# ProDoc_dogo-Lab_esp32c3__shockerMini_V1_.net
KiCad netlist of a schematic drawn in EasyEDA Pro
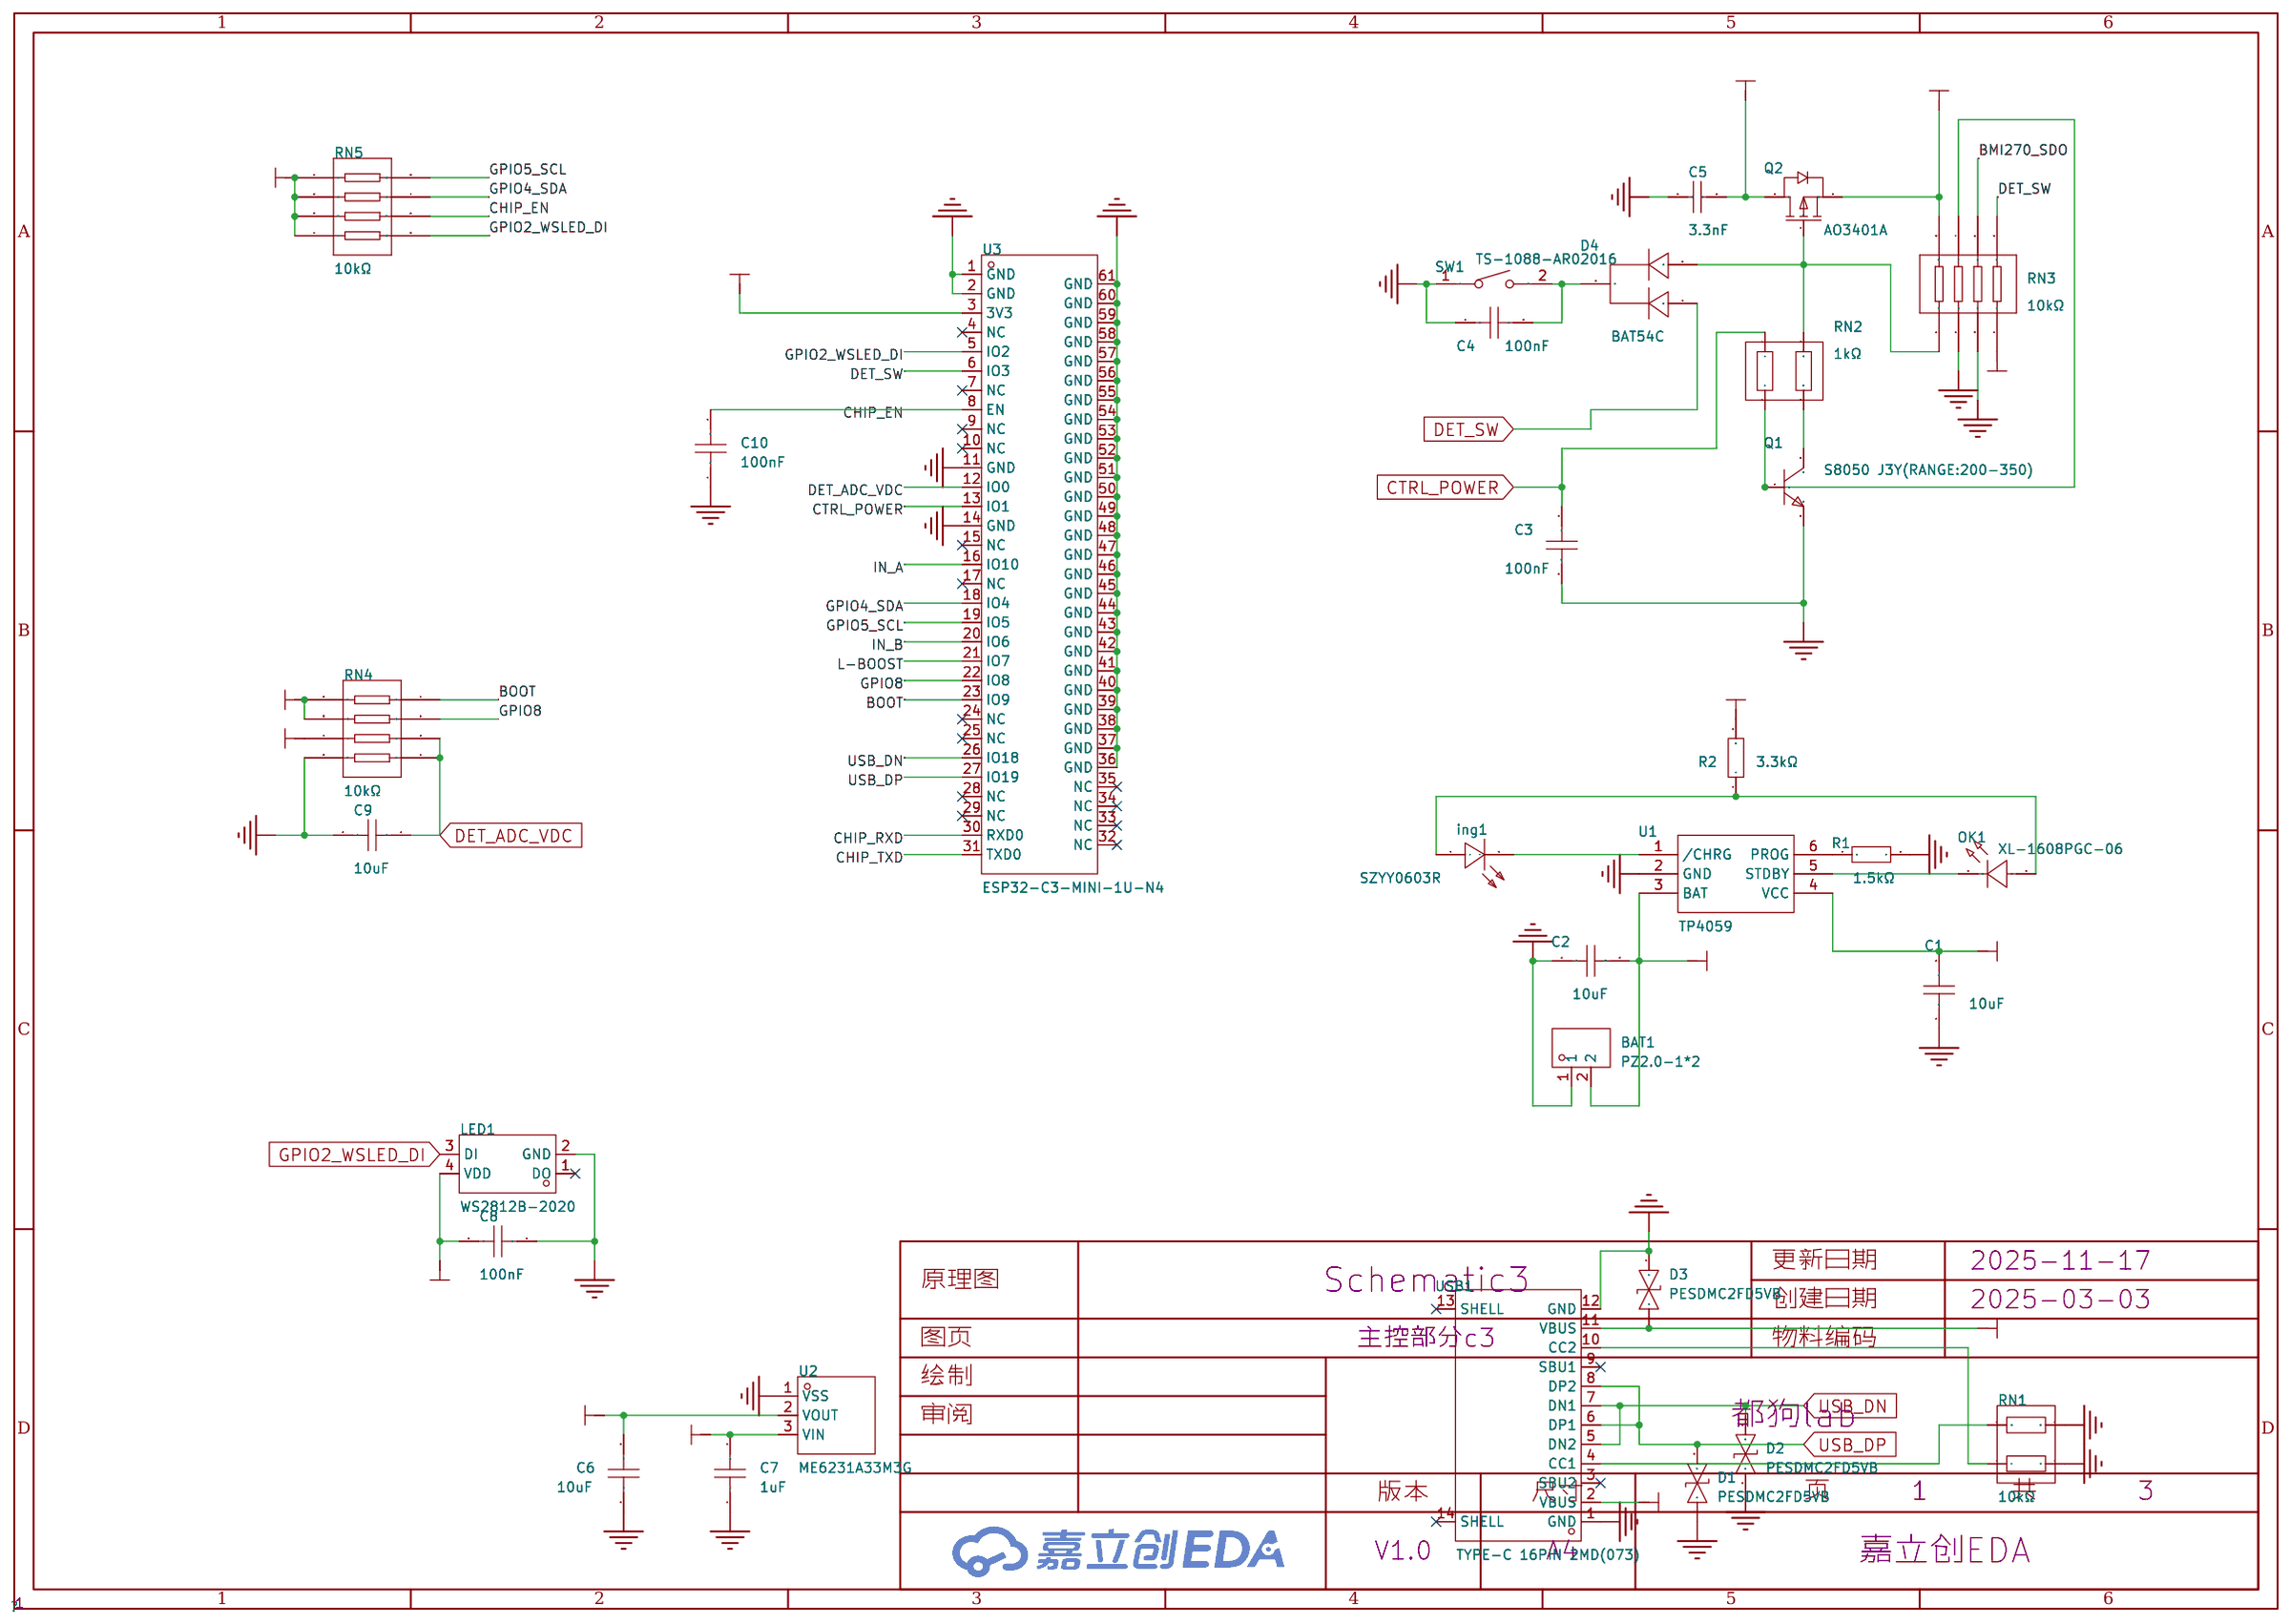
[diagram p0: 主控部分c3]
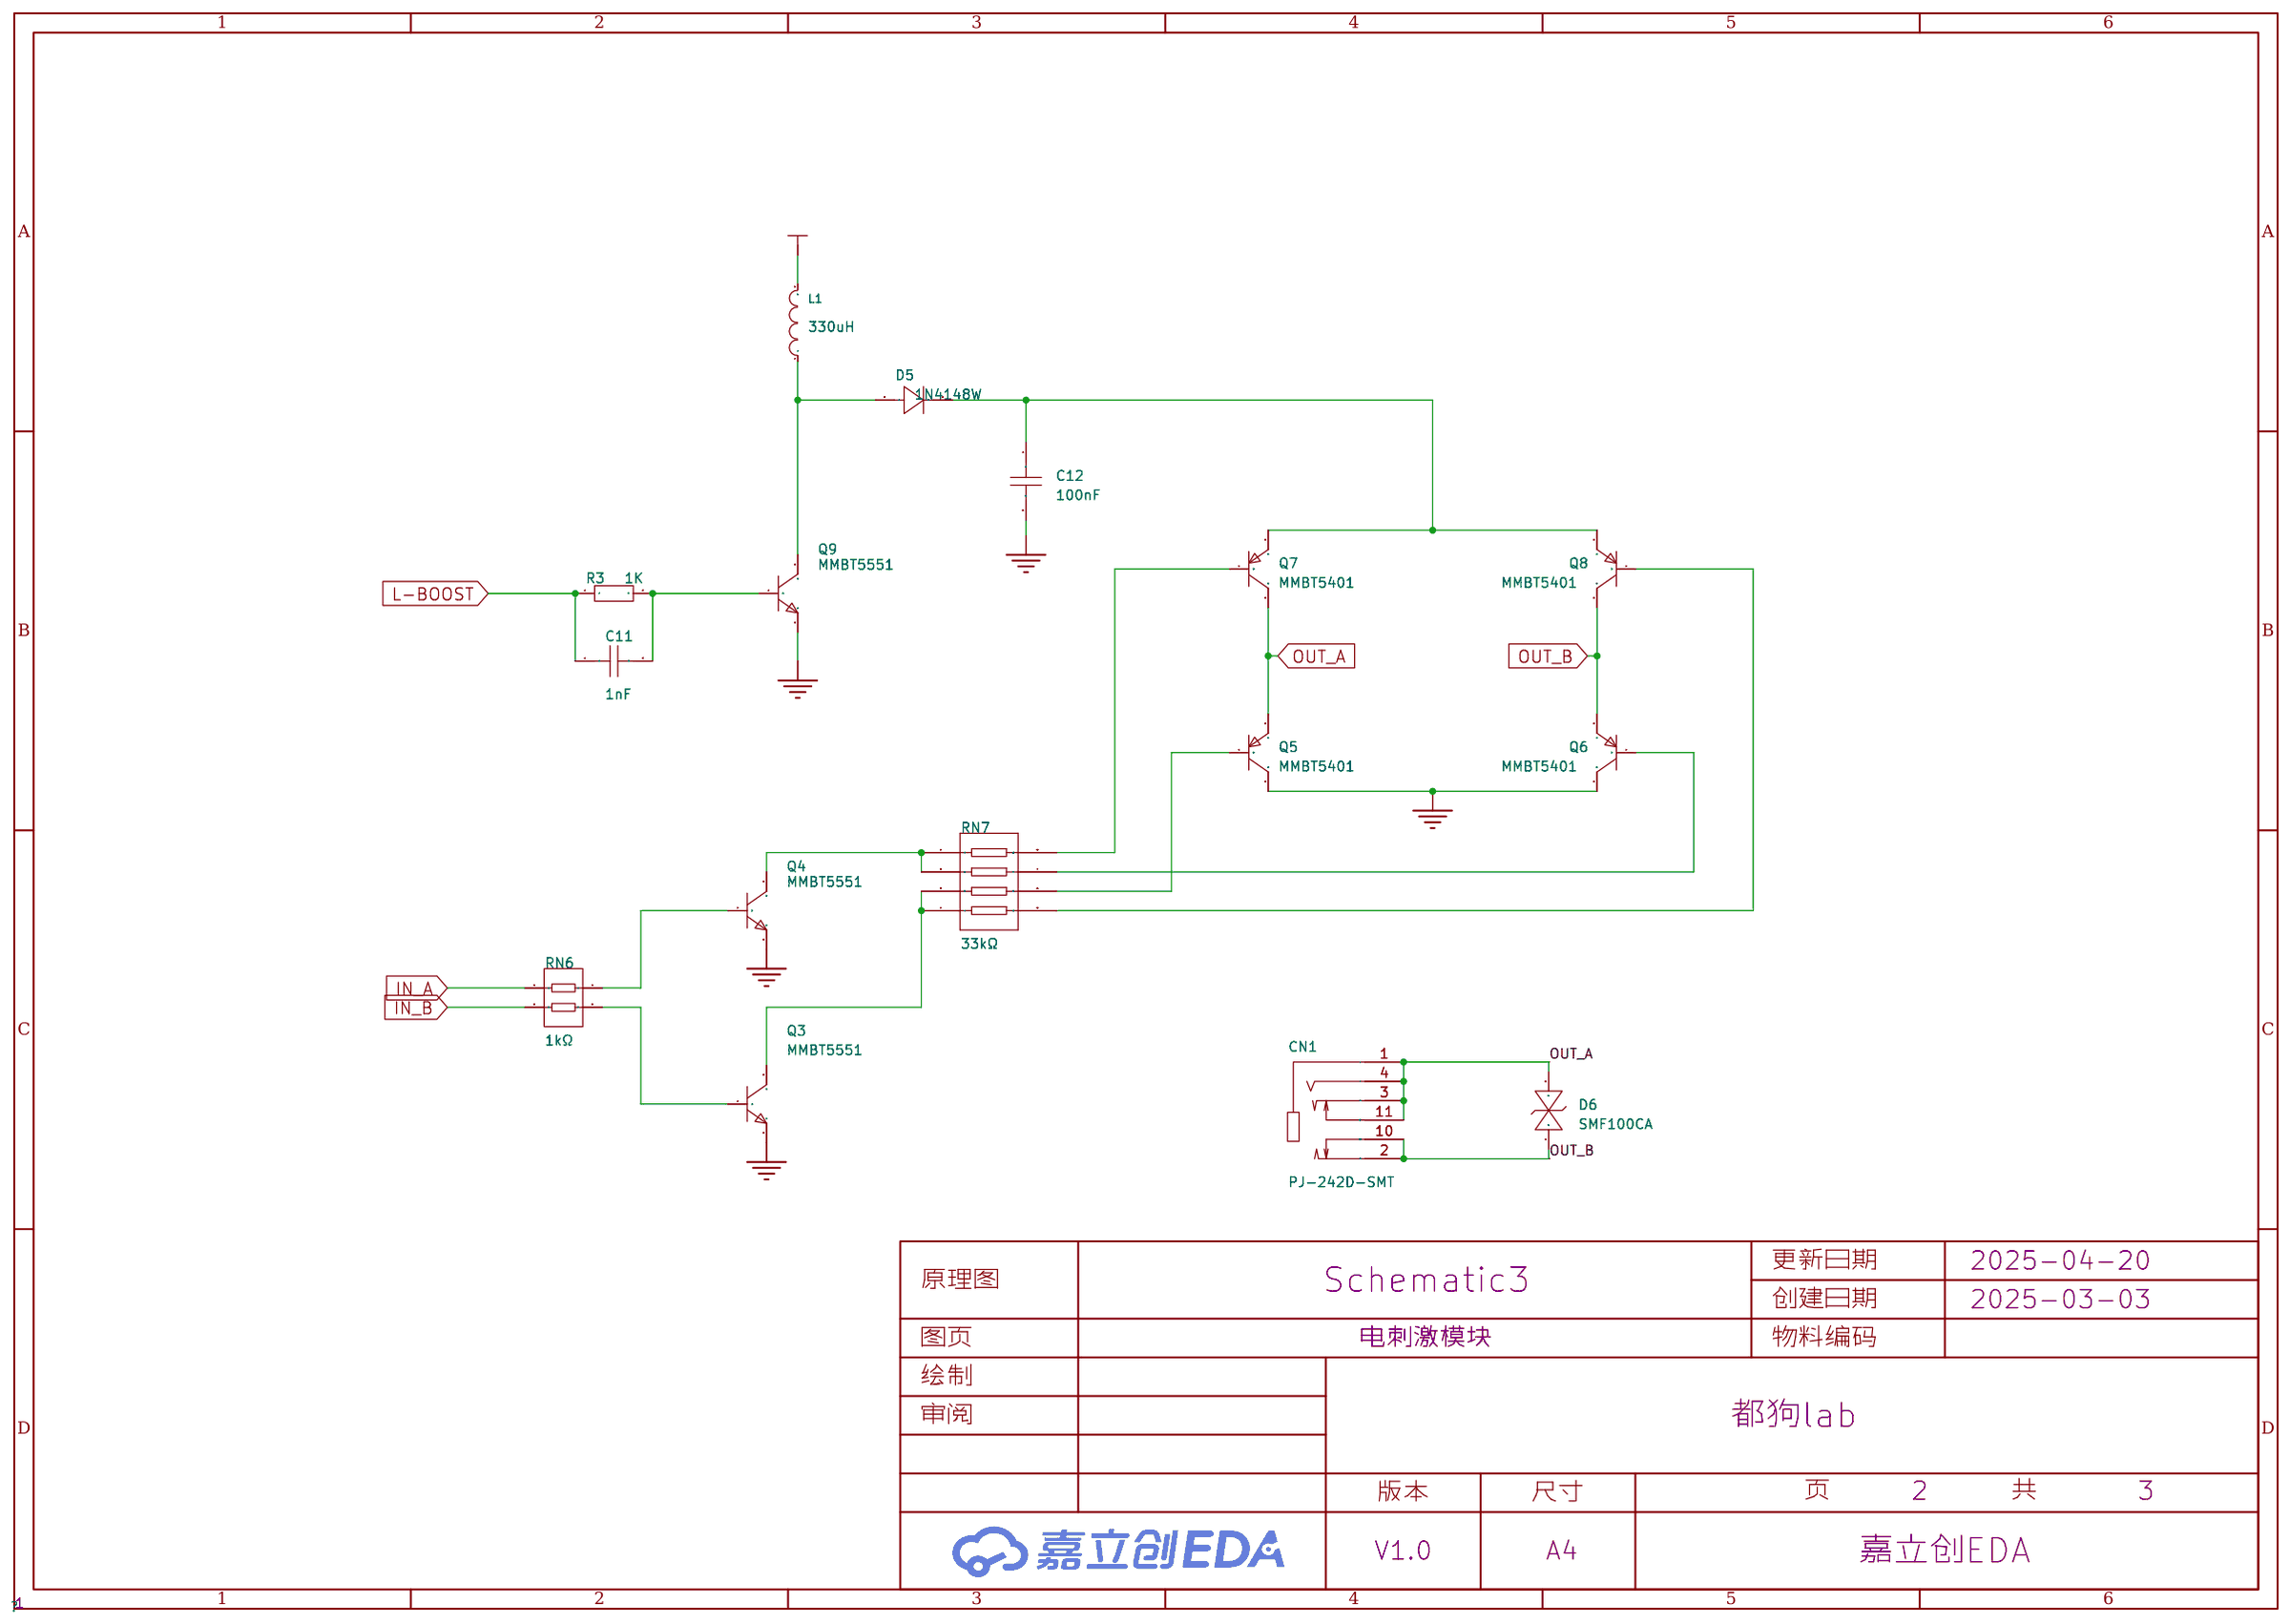
[diagram p1: 电刺激模块]
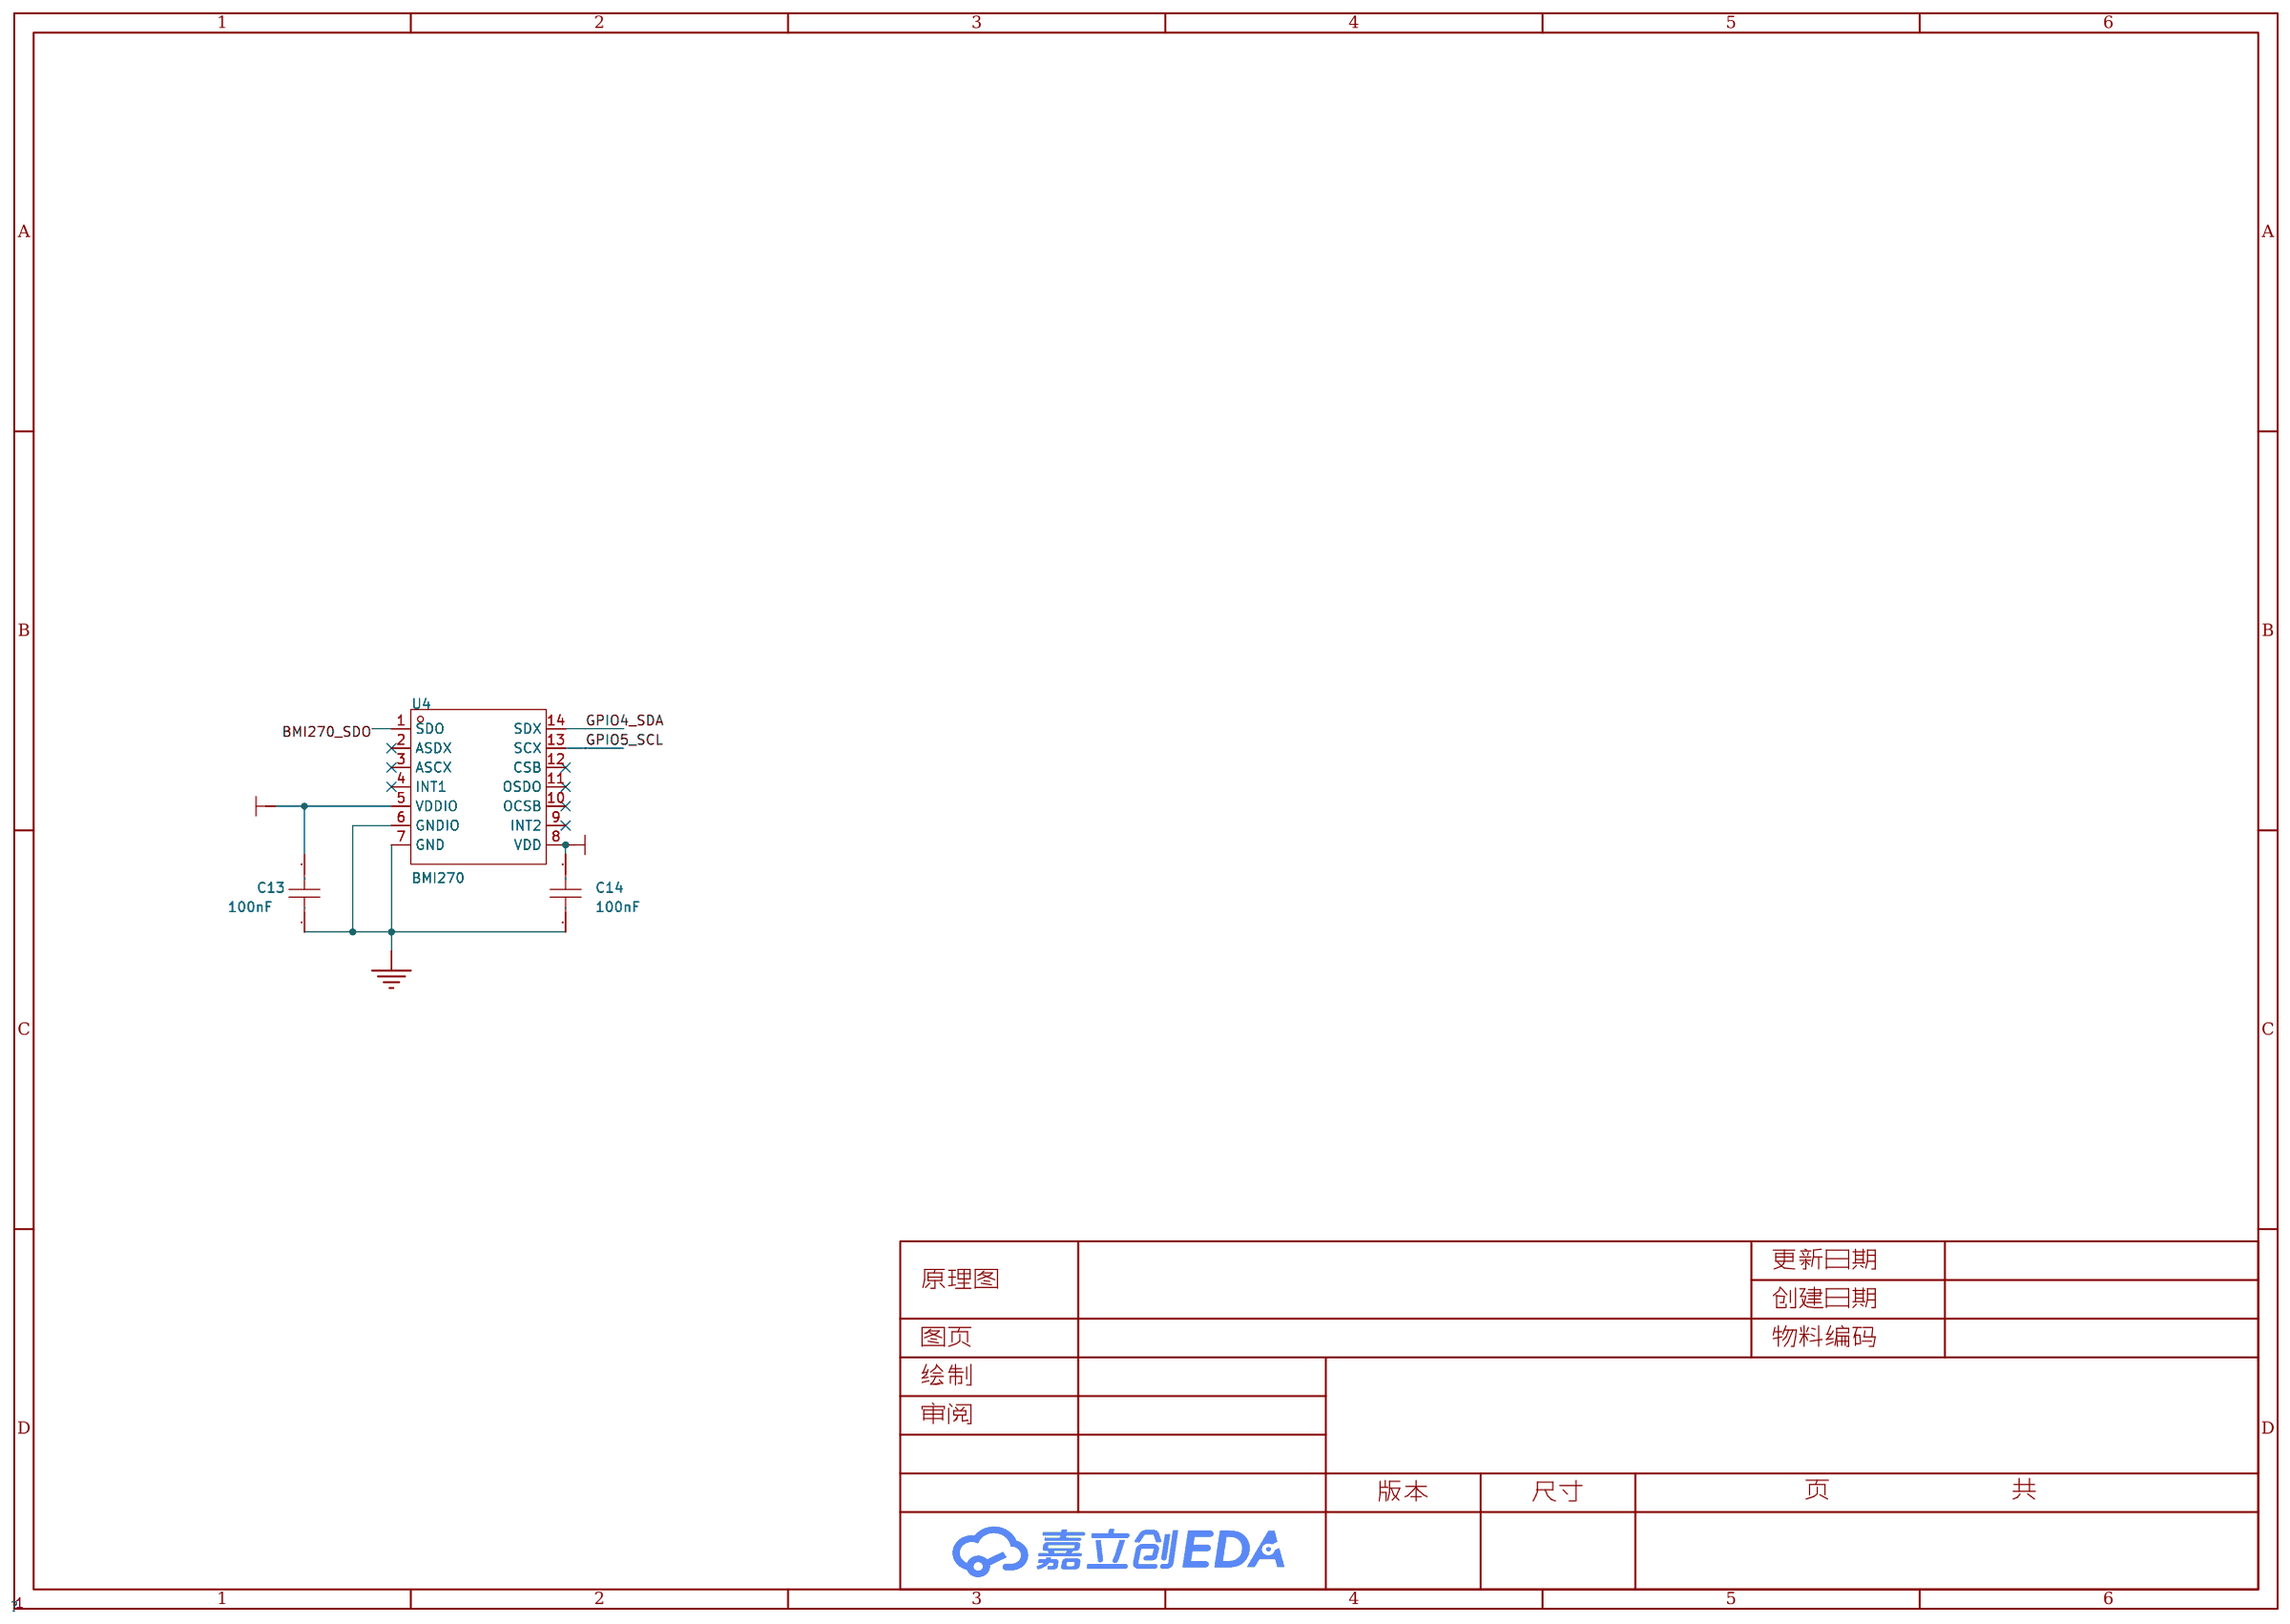
[diagram p2: 体动传感器]

(export (version "E")
  (design (tool "Eeschema 10.0.6"))
  (components
    (comp (ref "BAT1")
      (value "PZ2.0-1*2")
      (footprint "easyedapro:HDR-TH_2P-P2.00-V-M")
      (description "插针结构:1x2P;间距:2mm;安装类型:直插;排数:单排;总PIN位数:2P;触头镀层:金;")
      (fields (field (name "Manufacturer") "ZHOURI(洲日)"))
      (libsource (lib "easyedapro") (part "PZ2.0-1*2"))
    )
    (comp (ref "C1")
      (value "10uF")
      (fields
        (field (name "Manufacturer Part") "CL05A106MP5NUNC")
        (field (name "Manufacturer") "SAMSUNG(三星)")
      )
      (libsource (lib "easyedapro") (part "CL10A106KP8NNNC"))
    )
    (comp (ref "C2")
      (value "10uF")
      (fields
        (field (name "Manufacturer Part") "CL05A106MP5NUNC")
        (field (name "Manufacturer") "SAMSUNG(三星)")
      )
      (libsource (lib "easyedapro") (part "CL10A106MA8NRNC"))
    )
    (comp (ref "C3")
      (value "100nF")
      (fields
        (field (name "Manufacturer Part") "CL05B104KB54PNC")
        (field (name "Manufacturer") "SAMSUNG(三星)")
      )
      (libsource (lib "easyedapro") (part "CL10B104KB8NNNC"))
    )
    (comp (ref "C4")
      (value "100nF")
      (fields
        (field (name "Manufacturer Part") "CL05B104KB54PNC")
        (field (name "Manufacturer") "SAMSUNG(三星)")
      )
      (libsource (lib "easyedapro") (part "CL10B104KB8NNNC"))
    )
    (comp (ref "C5")
      (value "3.3nF")
      (fields
        (field (name "Manufacturer Part") "CL05B332KB5NNNC")
        (field (name "Manufacturer") "SAMSUNG(三星)")
      )
      (libsource (lib "easyedapro") (part "CL10B332KB8NNNC"))
    )
    (comp (ref "C6")
      (value "10uF")
      (fields
        (field (name "Manufacturer Part") "CL05A106MP5NUNC")
        (field (name "Manufacturer") "SAMSUNG(三星)")
      )
      (libsource (lib "easyedapro") (part "CL10A106KP8NNNC"))
    )
    (comp (ref "C7")
      (value "1uF")
      (fields
        (field (name "Manufacturer Part") "CL05A105KA5NQNC")
        (field (name "Manufacturer") "SAMSUNG(三星)")
      )
      (libsource (lib "easyedapro") (part "CL10B104KB8NNNC"))
    )
    (comp (ref "C8")
      (value "100nF")
      (fields
        (field (name "Manufacturer Part") "CL05B104KB54PNC")
        (field (name "Manufacturer") "SAMSUNG(三星)")
      )
      (libsource (lib "easyedapro") (part "CL10B104KB8NNNC"))
    )
    (comp (ref "C9")
      (value "10uF")
      (fields
        (field (name "Manufacturer Part") "CL05A106MP5NUNC")
        (field (name "Manufacturer") "SAMSUNG(三星)")
      )
      (libsource (lib "easyedapro") (part "CL10A106KP8NNNC"))
    )
    (comp (ref "C10")
      (value "100nF")
      (fields
        (field (name "Manufacturer Part") "CL05B104KB54PNC")
        (field (name "Manufacturer") "SAMSUNG(三星)")
      )
      (libsource (lib "easyedapro") (part "CL10B104KB8NNNC"))
    )
    (comp (ref "D1")
      (value "PESDMC2FD5VB")
      (footprint "easyedapro:DFN1006-2L-BI")
      (description "极性:双向;反向截止电压(Vrwm):5V;最大钳位电压:11V;峰值脉冲电流(Ipp):4A;")
      (fields (field (name "Manufacturer") "Prisemi(芯导)"))
      (libsource (lib "easyedapro") (part "PESDMC2FD5VB"))
    )
    (comp (ref "D2")
      (value "PESDMC2FD5VB")
      (footprint "easyedapro:DFN1006-2L-BI")
      (description "极性:双向;反向截止电压(Vrwm):5V;最大钳位电压:11V;峰值脉冲电流(Ipp):4A;")
      (fields (field (name "Manufacturer") "Prisemi(芯导)"))
      (libsource (lib "easyedapro") (part "PESDMC2FD5VB"))
    )
    (comp (ref "D3")
      (value "PESDMC2FD5VB")
      (footprint "easyedapro:DFN1006-2L-BI")
      (description "极性:双向;反向截止电压(Vrwm):5V;最大钳位电压:11V;峰值脉冲电流(Ipp):4A;")
      (fields (field (name "Manufacturer") "Prisemi(芯导)"))
      (libsource (lib "easyedapro") (part "PESDMC2FD5VB"))
    )
    (comp (ref "D4")
      (value "BAT54C")
      (footprint "easyedapro:SOT-23-3_L2.9-W1.6-P1.90-LS2.8-BR")
      (description "二极管配置:-;正向压降(Vf):1V@100mA;直流反向耐压(Vr):30V;平均整流电流(Io):200mA;")
      (fields (field (name "Manufacturer") "CJ(江苏长电/长晶)"))
      (libsource (lib "easyedapro") (part "BAT54C"))
    )
    (comp (ref "ing1")
      (value "SZYY0603R")
      (footprint "easyedapro:LED0603-R-RD")
      (fields (field (name "Manufacturer") "yongyu(永裕光电)"))
      (libsource (lib "easyedapro") (part "SZYY0603R"))
    )
    (comp (ref "LED1")
      (value "WS2812B-2020")
      (footprint "easyedapro:LED-SMD_4P-L2.0-W2.0-TL_WS2812B-2020")
      (description "12mA，小尺寸，高亮，用于小间距，小尺寸产品（注意防潮，请查阅规格书中对应具体内容）")
      (fields (field (name "Manufacturer") "worldsemi"))
      (libsource (lib "easyedapro") (part "WS2812B-2020"))
    )
    (comp (ref "OK1")
      (value "XL-1608PGC-06")
      (footprint "easyedapro:LED0603-RD_GREEN")
      (fields (field (name "Manufacturer") "XINGLIGHT(成兴光)"))
      (libsource (lib "easyedapro") (part "XL-1608PGC-06"))
    )
    (comp (ref "Q1")
      (value "S8050 J3Y(RANGE:200-350)")
      (footprint "easyedapro:SOT-23-3_L3.0-W1.7-P0.95-LS2.9-BR")
      (description "晶体管类型:NPN;集电极电流(Ic):500mA;集射极击穿电压(Vceo):25V;功率(Pd):300mW;直流电流增益(hFE@Ic,Vce):200@500mA,1V;")
      (fields (field (name "Manufacturer") "CJ(江苏长电/长晶)"))
      (libsource (lib "easyedapro") (part "S8050_C2146"))
    )
    (comp (ref "Q2")
      (value "AO3401A")
      (footprint "easyedapro:SOT-23_L2.9-W1.3-P1.90-LS2.4-BR")
      (fields (field (name "Manufacturer") "UMW(友台半导体)"))
      (libsource (lib "easyedapro") (part "AO3401A_C347476"))
    )
    (comp (ref "R1")
      (value "1.5kΩ")
      (fields (field (name "Manufacturer Part") "RC0402FR-071K5L") (field (name "Manufacturer") "YAGEO(国巨)"))
      (libsource (lib "easyedapro") (part "0603WAF1501T5E"))
    )
    (comp (ref "R2")
      (value "3.3kΩ")
      (fields (field (name "Manufacturer Part") "CR0402FF3301G") (field (name "Manufacturer") "LIZ(丽智电子)"))
      (libsource (lib "easyedapro") (part "0603WAF3301T5E"))
    )
    (comp (ref "RN1")
      (value "10kΩ")
      (footprint "easyedapro:RES-ARRAY-SMD_0404-4P-L1.0-W1.0-BL")
      (description "电阻器数:2;阻值:10kΩ;精度:±5%;单个元件功率:62.5mW;温度系数:±200ppm/°C;")
      (fields (field (name "Manufacturer Part") "YC122-JR-0710KL") (field (name "Manufacturer") "YAGEO(国巨)"))
      (libsource (lib "easyedapro") (part "YC122-JR-0710KL"))
    )
    (comp (ref "RN2")
      (value "1kΩ")
      (footprint "easyedapro:RES-ARRAY-SMD_0404-4P-L1.0-W1.0-BL")
      (description "电阻器数:2;阻值:1kΩ;精度:±5%;单个元件功率:62.5mW;温度系数:±200ppm/°C;")
      (fields (field (name "Manufacturer Part") "YC122-JR-071KL") (field (name "Manufacturer") "YAGEO(国巨)"))
      (libsource (lib "easyedapro") (part "YC122-JR-071KL"))
    )
    (comp (ref "RN3")
      (value "10kΩ")
      (footprint "easyedapro:RES-ARRAY-SMD_0402-8P-L2.0-W1.0-BL")
      (description "电阻器数:4;阻值:10kΩ;精度:±1%;单个元件功率:62.5mW;温度系数:±200ppm/°C;")
      (fields (field (name "Manufacturer Part") "YC124-FR-0710KL") (field (name "Manufacturer") "YAGEO(国巨)"))
      (libsource (lib "easyedapro") (part "YC124-FR-0710KL"))
    )
    (comp (ref "RN4")
      (value "10kΩ")
      (footprint "easyedapro:RES-ARRAY-SMD_0402-8P-L2.0-W1.0-BL")
      (description "电阻器数:4;阻值:10kΩ;精度:±1%;单个元件功率:62.5mW;温度系数:±200ppm/°C;")
      (fields (field (name "Manufacturer Part") "YC124-FR-0710KL") (field (name "Manufacturer") "YAGEO(国巨)"))
      (libsource (lib "easyedapro") (part "YC124-FR-0710KL"))
    )
    (comp (ref "RN5")
      (value "10kΩ")
      (footprint "easyedapro:RES-ARRAY-SMD_0402-8P-L2.0-W1.0-BL")
      (description "电阻器数:4;阻值:10kΩ;精度:±1%;单个元件功率:62.5mW;温度系数:±200ppm/°C;")
      (fields (field (name "Manufacturer Part") "YC124-FR-0710KL") (field (name "Manufacturer") "YAGEO(国巨)"))
      (libsource (lib "easyedapro") (part "YC124-FR-0710KL"))
    )
    (comp (ref "SW1")
      (value "TS-1088-AR02016")
      (footprint "easyedapro:SW-SMD_L3.9-W3.0-P4.45")
      (fields (field (name "Manufacturer") "XUNPU(讯普)"))
      (libsource (lib "easyedapro") (part "TS-1088-AR02016"))
    )
    (comp (ref "U1")
      (value "TP4059")
      (footprint "easyedapro:SOT-23-6_L2.9-W1.6-P0.95-LS2.8-BR")
      (description "600mA 线性锂电池充电IC")
      (fields (field (name "Manufacturer") "TOPPOWER(南京拓微)"))
      (libsource (lib "easyedapro") (part "TP4059"))
    )
    (comp (ref "U2")
      (value "ME6231A33M3G")
      (footprint "easyedapro:SOT-23-3_L2.9-W1.6-P1.90-LS2.8-BR")
      (description "输出类型:固定;最大输入电压:18V;输出电压:3.3V;输出电流:500mA;电源纹波抑制比(PSRR):76dB@(100Hz);输出极性:正极;")
      (fields (field (name "Manufacturer") "MICRONE(南京微盟)"))
      (libsource (lib "easyedapro") (part "ME6231A33M3G"))
    )
    (comp (ref "U3")
      (value "ESP32-C3-MINI-1U-N4")
      (footprint "easyedapro:WIFIM-SMD_61P-L13.2-W12.5-P0.80")
      (fields (field (name "Manufacturer") "ESPRESSIF(乐鑫)"))
      (libsource (lib "easyedapro") (part "ESP32-C3-MINI-1U-N4"))
    )
    (comp (ref "USB1")
      (value "TYPE-C 16PIN 2MD(073)")
      (footprint "easyedapro:USB-C-SMD_TYPE-C-6PIN-2MD-073")
      (description "连接器类型:Type-C;标准:USB 3.1;公母:母;安装方式:卧贴;触点数量:16P;端口数量:1;额定电流 - 电源:5A;工作温度范围:-25°C~+85°C;")
      (fields (field (name "Manufacturer") "SHOU HAN(首韩)"))
      (libsource (lib "easyedapro") (part "TYPE-C 16PIN 2MD(073)"))
    )
    (comp (ref "C11")
      (value "1nF")
      (fields
        (field (name "Manufacturer Part") "CL10B102KC8NNNC")
        (field (name "Manufacturer") "SAMSUNG(三星)")
      )
      (libsource (lib "easyedapro") (part "CapAcitance"))
    )
    (comp (ref "C12")
      (value "100nF")
      (fields (field (name "Manufacturer Part") "1206B104K101NT") (field (name "Manufacturer") "FH(风华)"))
      (libsource (lib "easyedapro") (part "CapAcitance"))
    )
    (comp (ref "CN1")
      (value "PJ-242D-SMT")
      (footprint "easyedapro:AUDIO-SMD_PJ-242D-SMT")
      (description "连接器类型:2.5mm耳机座;额定电流:500mA;额定电压:30V;工作温度范围:-20°C~+70°C;焊接温度(最大值):235°C;")
      (fields (field (name "Manufacturer") "XKB Connectivity(中国星坤)"))
      (libsource (lib "easyedapro") (part "PJ-242D-SMT"))
    )
    (comp (ref "D5")
      (value "1N4148W")
      (fields (field (name "Manufacturer") "CJ(江苏长电/长晶)"))
      (libsource (lib "easyedapro") (part "D_1N4007"))
    )
    (comp (ref "D6")
      (value "SMF100CA")
      (fields (field (name "Manufacturer") "TWGMC(台湾迪嘉)"))
      (libsource (lib "easyedapro") (part "SMAJ100CA_C726810"))
    )
    (comp (ref "L1")
      (value "330uH")
      (fields (field (name "Manufacturer Part") "FNR4030S331MT") (field (name "Manufacturer") "cjiang(长江微电)"))
      (libsource (lib "easyedapro") (part "SDFL1608S100KTF"))
    )
    (comp (ref "Q3")
      (value "MMBT5551")
      (footprint "easyedapro:SOT-23-3_L2.9-W1.3-P1.90-LS2.4-BR")
      (description "晶体管类型:-;集电极电流(Ic):600mA;集射极击穿电压(Vceo):160V;功率(Pd):300mW;直流电流增益(hFE@Ic,Vce):100@10mA,5V;")
      (fields (field (name "Manufacturer") "BORN(伯恩半导体)"))
      (libsource (lib "easyedapro") (part "MMBT5551_C511877"))
    )
    (comp (ref "Q4")
      (value "MMBT5551")
      (footprint "easyedapro:SOT-23-3_L2.9-W1.3-P1.90-LS2.4-BR")
      (description "晶体管类型:-;集电极电流(Ic):600mA;集射极击穿电压(Vceo):160V;功率(Pd):300mW;直流电流增益(hFE@Ic,Vce):100@10mA,5V;")
      (fields (field (name "Manufacturer") "BORN(伯恩半导体)"))
      (libsource (lib "easyedapro") (part "MMBT5551_C511877"))
    )
    (comp (ref "Q5")
      (value "MMBT5401")
      (footprint "easyedapro:SOT-23-3_L2.9-W1.3-P1.90-LS2.4-BR")
      (description "晶体管类型:PNP;集电极电流(Ic):600mA;集射极击穿电压(Vceo):150V;功率(Pd):300mW;直流电流增益(hFE@Ic,Vce):200@10mA,5V;")
      (fields (field (name "Manufacturer") "CJ(江苏长电/长晶)"))
      (libsource (lib "easyedapro") (part "MMBT5401"))
    )
    (comp (ref "Q6")
      (value "MMBT5401")
      (footprint "easyedapro:SOT-23-3_L2.9-W1.3-P1.90-LS2.4-BR")
      (description "晶体管类型:PNP;集电极电流(Ic):600mA;集射极击穿电压(Vceo):150V;功率(Pd):300mW;直流电流增益(hFE@Ic,Vce):200@10mA,5V;")
      (fields (field (name "Manufacturer") "CJ(江苏长电/长晶)"))
      (libsource (lib "easyedapro") (part "MMBT5401"))
    )
    (comp (ref "Q7")
      (value "MMBT5401")
      (footprint "easyedapro:SOT-23-3_L2.9-W1.3-P1.90-LS2.4-BR")
      (description "晶体管类型:PNP;集电极电流(Ic):600mA;集射极击穿电压(Vceo):150V;功率(Pd):300mW;直流电流增益(hFE@Ic,Vce):200@10mA,5V;")
      (fields (field (name "Manufacturer") "CJ(江苏长电/长晶)"))
      (libsource (lib "easyedapro") (part "MMBT5401"))
    )
    (comp (ref "Q8")
      (value "MMBT5401")
      (footprint "easyedapro:SOT-23-3_L2.9-W1.3-P1.90-LS2.4-BR")
      (description "晶体管类型:PNP;集电极电流(Ic):600mA;集射极击穿电压(Vceo):150V;功率(Pd):300mW;直流电流增益(hFE@Ic,Vce):200@10mA,5V;")
      (fields (field (name "Manufacturer") "CJ(江苏长电/长晶)"))
      (libsource (lib "easyedapro") (part "MMBT5401"))
    )
    (comp (ref "Q9")
      (value "MMBT5551")
      (footprint "easyedapro:SOT-23-3_L2.9-W1.3-P1.90-LS2.4-BR")
      (description "晶体管类型:-;集电极电流(Ic):600mA;集射极击穿电压(Vceo):160V;功率(Pd):300mW;直流电流增益(hFE@Ic,Vce):100@10mA,5V;")
      (fields (field (name "Manufacturer") "BORN(伯恩半导体)"))
      (libsource (lib "easyedapro") (part "MMBT5551_C511877"))
    )
    (comp (ref "R3") (value "1K") (footprint "easyedapro:R0603") (libsource (lib "easyedapro") (part "电阻")))
    (comp (ref "RN6")
      (value "1kΩ")
      (footprint "easyedapro:RES-ARRAY-SMD_0603-4P-L1.6-W1.6-BL")
      (description "电阻器数:2;阻值:1kΩ;精度:±5%;单个元件功率:62.5mW;温度系数:±200ppm/°C;")
      (fields
        (field (name "Manufacturer Part") "2D03WGJ0102T5E")
        (field (name "Manufacturer") "UNI-ROYAL(厚声)")
      )
      (libsource (lib "easyedapro") (part "2D03WGJ0102T5E"))
    )
    (comp (ref "RN7")
      (value "33kΩ")
      (footprint "easyedapro:RES-ARRAY-SMD_0603-8P-L3.2-W1.6-BL")
      (description "电阻器数:4;阻值:33kΩ;精度:±5%;单个元件功率:62.5mW;温度系数:±200ppm/°C;")
      (fields
        (field (name "Manufacturer Part") "4D03WGJ0333T5E")
        (field (name "Manufacturer") "UNI-ROYAL(厚声)")
      )
      (libsource (lib "easyedapro") (part "4D03WGJ0333T5E"))
    )
    (comp (ref "C13")
      (value "100nF")
      (footprint "easyedapro:C0402")
      (description "容值:100nF;精度:±10%;额定电压:50V;材质(温度系数):X7R;")
      (fields
        (field (name "Manufacturer Part") "CL05B104KB54PNC")
        (field (name "Manufacturer") "SAMSUNG(三星)")
      )
      (libsource (lib "easyedapro") (part "CL05B104KB54PNC"))
    )
    (comp (ref "C14")
      (value "100nF")
      (footprint "easyedapro:C0402")
      (description "容值:100nF;精度:±10%;额定电压:50V;材质(温度系数):X7R;")
      (fields
        (field (name "Manufacturer Part") "CL05B104KB54PNC")
        (field (name "Manufacturer") "SAMSUNG(三星)")
      )
      (libsource (lib "easyedapro") (part "CL05B104KB54PNC"))
    )
    (comp (ref "U4")
      (value "BMI270")
      (footprint "easyedapro:LGA-14_L3.0-W2.5-P0.50-BR")
      (description "传感器类型:加速度计陀螺仪;")
      (fields (field (name "Manufacturer") "Bosch(博世)"))
      (libsource (lib "easyedapro") (part "BMI270"))
    )
  )
  (nets
    (net (code "1") (name "3V3") (class "Default")
      (node (ref "C13") (pin "2") (pinfunction "2_2") (pintype "unspecified"))
      (node (ref "C14") (pin "2") (pinfunction "2_2") (pintype "unspecified"))
      (node (ref "C6") (pin "2") (pinfunction "2_2") (pintype "unspecified"))
      (node (ref "RN3") (pin "4") (pinfunction "4_4") (pintype "input"))
      (node (ref "RN4") (pin "5") (pinfunction "5_5") (pintype "input"))
      (node (ref "RN4") (pin "6") (pinfunction "6_6") (pintype "input"))
      (node (ref "RN5") (pin "1") (pinfunction "1_1") (pintype "input"))
      (node (ref "RN5") (pin "2") (pinfunction "2_2") (pintype "input"))
      (node (ref "RN5") (pin "3") (pinfunction "3_3") (pintype "input"))
      (node (ref "RN5") (pin "4") (pinfunction "4_4") (pintype "input"))
      (node (ref "U2") (pin "2") (pinfunction "VOUT_2") (pintype "unspecified"))
      (node (ref "U3") (pin "3") (pinfunction "3V3_3") (pintype "unspecified"))
      (node (ref "U4") (pin "5") (pinfunction "VDDIO_5") (pintype "unspecified"))
      (node (ref "U4") (pin "8") (pinfunction "VDD_8") (pintype "unspecified"))
    )
    (net (code "2") (name "BMI270_SDO") (class "Default")
      (node (ref "RN3") (pin "6") (pinfunction "6_6") (pintype "input"))
      (node (ref "U4") (pin "1") (pinfunction "SDO_1") (pintype "unspecified"))
    )
    (net (code "3") (name "BOOT") (class "Default")
      (node (ref "RN4") (pin "4") (pinfunction "4_4") (pintype "input"))
      (node (ref "U3") (pin "23") (pinfunction "IO9_23") (pintype "unspecified"))
    )
    (net (code "4") (name "CHIP_EN") (class "Default")
      (node (ref "C10") (pin "2") (pinfunction "2_2") (pintype "unspecified"))
      (node (ref "RN5") (pin "6") (pinfunction "6_6") (pintype "input"))
      (node (ref "U3") (pin "8") (pinfunction "EN_8") (pintype "unspecified"))
    )
    (net (code "5") (name "CHIP_RXD") (class "Default")
      (node (ref "U3") (pin "30") (pinfunction "RXD0_30") (pintype "unspecified"))
    )
    (net (code "6") (name "CHIP_TXD") (class "Default")
      (node (ref "U3") (pin "31") (pinfunction "TXD0_31") (pintype "unspecified"))
    )
    (net (code "7") (name "CTRL_POWER") (class "Default")
      (node (ref "C3") (pin "1") (pinfunction "1_1") (pintype "unspecified"))
      (node (ref "RN2") (pin "4") (pinfunction "4_4") (pintype "unspecified"))
      (node (ref "U3") (pin "13") (pinfunction "IO1_13") (pintype "unspecified"))
    )
    (net (code "8") (name "DET_ADC_VDC") (class "Default")
      (node (ref "C9") (pin "1") (pinfunction "1_1") (pintype "unspecified"))
      (node (ref "RN4") (pin "1") (pinfunction "1_1") (pintype "input"))
      (node (ref "RN4") (pin "2") (pinfunction "2_2") (pintype "input"))
      (node (ref "U3") (pin "12") (pinfunction "IO0_12") (pintype "unspecified"))
    )
    (net (code "9") (name "DET_SW") (class "Default")
      (node (ref "D4") (pin "1") (pinfunction "A1_1") (pintype "unspecified"))
      (node (ref "RN3") (pin "5") (pinfunction "5_5") (pintype "input"))
      (node (ref "U3") (pin "6") (pinfunction "IO3_6") (pintype "unspecified"))
    )
    (net (code "10") (name "GND") (class "Default")
      (node (ref "BAT1") (pin "1") (pinfunction "1_1") (pintype "unspecified"))
      (node (ref "C1") (pin "1") (pinfunction "1_1") (pintype "unspecified"))
      (node (ref "C10") (pin "1") (pinfunction "1_1") (pintype "unspecified"))
      (node (ref "C12") (pin "2") (pinfunction "2_2") (pintype "input"))
      (node (ref "C13") (pin "1") (pinfunction "1_1") (pintype "unspecified"))
      (node (ref "C14") (pin "1") (pinfunction "1_1") (pintype "unspecified"))
      (node (ref "C2") (pin "1") (pinfunction "1_1") (pintype "unspecified"))
      (node (ref "C3") (pin "2") (pinfunction "2_2") (pintype "unspecified"))
      (node (ref "C4") (pin "1") (pinfunction "1_1") (pintype "unspecified"))
      (node (ref "C5") (pin "1") (pinfunction "1_1") (pintype "input"))
      (node (ref "C6") (pin "1") (pinfunction "1_1") (pintype "unspecified"))
      (node (ref "C7") (pin "1") (pinfunction "1_1") (pintype "unspecified"))
      (node (ref "C8") (pin "1") (pinfunction "1_1") (pintype "unspecified"))
      (node (ref "C9") (pin "2") (pinfunction "2_2") (pintype "unspecified"))
      (node (ref "D1") (pin "1") (pinfunction "1_1") (pintype "unspecified"))
      (node (ref "D2") (pin "1") (pinfunction "1_1") (pintype "unspecified"))
      (node (ref "D3") (pin "2") (pinfunction "2_2") (pintype "unspecified"))
      (node (ref "LED1") (pin "2") (pinfunction "GND_2") (pintype "unspecified"))
      (node (ref "Q1") (pin "2") (pinfunction "E_2") (pintype "unspecified"))
      (node (ref "Q3") (pin "2") (pinfunction "E_2") (pintype "input"))
      (node (ref "Q4") (pin "2") (pinfunction "E_2") (pintype "input"))
      (node (ref "Q5") (pin "3") (pinfunction "C_3") (pintype "unspecified"))
      (node (ref "Q6") (pin "3") (pinfunction "C_3") (pintype "unspecified"))
      (node (ref "Q9") (pin "2") (pinfunction "E_2") (pintype "input"))
      (node (ref "R1") (pin "2") (pinfunction "2_2") (pintype "input"))
      (node (ref "RN1") (pin "1") (pinfunction "1_1") (pintype "unspecified"))
      (node (ref "RN1") (pin "2") (pinfunction "2_2") (pintype "unspecified"))
      (node (ref "RN3") (pin "2") (pinfunction "2_2") (pintype "input"))
      (node (ref "RN3") (pin "3") (pinfunction "3_3") (pintype "input"))
      (node (ref "RN4") (pin "8") (pinfunction "8_8") (pintype "input"))
      (node (ref "SW1") (pin "1") (pinfunction "1_1") (pintype "unspecified"))
      (node (ref "U1") (pin "2") (pinfunction "GND_2") (pintype "input"))
      (node (ref "U2") (pin "1") (pinfunction "VSS_1") (pintype "unspecified"))
      (node (ref "U3") (pin "1") (pinfunction "GND_1") (pintype "unspecified"))
      (node (ref "U3") (pin "11") (pinfunction "GND_11") (pintype "unspecified"))
      (node (ref "U3") (pin "14") (pinfunction "GND_14") (pintype "unspecified"))
      (node (ref "U3") (pin "2") (pinfunction "GND_2") (pintype "unspecified"))
      (node (ref "U3") (pin "36") (pinfunction "GND_36") (pintype "unspecified"))
      (node (ref "U3") (pin "37") (pinfunction "GND_37") (pintype "unspecified"))
      (node (ref "U3") (pin "38") (pinfunction "GND_38") (pintype "unspecified"))
      (node (ref "U3") (pin "39") (pinfunction "GND_39") (pintype "unspecified"))
      (node (ref "U3") (pin "40") (pinfunction "GND_40") (pintype "unspecified"))
      (node (ref "U3") (pin "41") (pinfunction "GND_41") (pintype "unspecified"))
      (node (ref "U3") (pin "42") (pinfunction "GND_42") (pintype "unspecified"))
      (node (ref "U3") (pin "43") (pinfunction "GND_43") (pintype "unspecified"))
      (node (ref "U3") (pin "44") (pinfunction "GND_44") (pintype "unspecified"))
      (node (ref "U3") (pin "45") (pinfunction "GND_45") (pintype "unspecified"))
      (node (ref "U3") (pin "46") (pinfunction "GND_46") (pintype "unspecified"))
      (node (ref "U3") (pin "47") (pinfunction "GND_47") (pintype "unspecified"))
      (node (ref "U3") (pin "48") (pinfunction "GND_48") (pintype "unspecified"))
      (node (ref "U3") (pin "49") (pinfunction "GND_49") (pintype "unspecified"))
      (node (ref "U3") (pin "50") (pinfunction "GND_50") (pintype "unspecified"))
      (node (ref "U3") (pin "51") (pinfunction "GND_51") (pintype "unspecified"))
      (node (ref "U3") (pin "52") (pinfunction "GND_52") (pintype "unspecified"))
      (node (ref "U3") (pin "53") (pinfunction "GND_53") (pintype "unspecified"))
      (node (ref "U3") (pin "54") (pinfunction "GND_54") (pintype "unspecified"))
      (node (ref "U3") (pin "55") (pinfunction "GND_55") (pintype "unspecified"))
      (node (ref "U3") (pin "56") (pinfunction "GND_56") (pintype "unspecified"))
      (node (ref "U3") (pin "57") (pinfunction "GND_57") (pintype "unspecified"))
      (node (ref "U3") (pin "58") (pinfunction "GND_58") (pintype "unspecified"))
      (node (ref "U3") (pin "59") (pinfunction "GND_59") (pintype "unspecified"))
      (node (ref "U3") (pin "60") (pinfunction "GND_60") (pintype "unspecified"))
      (node (ref "U3") (pin "61") (pinfunction "GND_61") (pintype "unspecified"))
      (node (ref "U4") (pin "6") (pinfunction "GNDIO_6") (pintype "unspecified"))
      (node (ref "U4") (pin "7") (pinfunction "GND_7") (pintype "unspecified"))
      (node (ref "USB1") (pin "1") (pinfunction "GND_1") (pintype "unspecified"))
      (node (ref "USB1") (pin "12") (pinfunction "GND_12") (pintype "unspecified"))
    )
    (net (code "11") (name "GPIO2_WSLED_DI") (class "Default")
      (node (ref "LED1") (pin "3") (pinfunction "DI_3") (pintype "unspecified"))
      (node (ref "RN5") (pin "5") (pinfunction "5_5") (pintype "input"))
      (node (ref "U3") (pin "5") (pinfunction "IO2_5") (pintype "unspecified"))
    )
    (net (code "12") (name "GPIO4_SDA") (class "Default")
      (node (ref "RN5") (pin "7") (pinfunction "7_7") (pintype "input"))
      (node (ref "U3") (pin "18") (pinfunction "IO4_18") (pintype "unspecified"))
      (node (ref "U4") (pin "14") (pinfunction "SDX_14") (pintype "unspecified"))
    )
    (net (code "13") (name "GPIO5_SCL") (class "Default")
      (node (ref "RN5") (pin "8") (pinfunction "8_8") (pintype "input"))
      (node (ref "U3") (pin "19") (pinfunction "IO5_19") (pintype "unspecified"))
      (node (ref "U4") (pin "13") (pinfunction "SCX_13") (pintype "unspecified"))
    )
    (net (code "14") (name "GPIO8") (class "Default")
      (node (ref "RN4") (pin "3") (pinfunction "3_3") (pintype "input"))
      (node (ref "U3") (pin "22") (pinfunction "IO8_22") (pintype "unspecified"))
    )
    (net (code "15") (name "IN_A") (class "Default")
      (node (ref "RN6") (pin "1") (pinfunction "1_1") (pintype "unspecified"))
      (node (ref "U3") (pin "16") (pinfunction "IO10_16") (pintype "unspecified"))
    )
    (net (code "16") (name "IN_B") (class "Default")
      (node (ref "RN6") (pin "2") (pinfunction "2_2") (pintype "unspecified"))
      (node (ref "U3") (pin "20") (pinfunction "IO6_20") (pintype "unspecified"))
    )
    (net (code "17") (name "L-BOOST") (class "Default")
      (node (ref "C11") (pin "1") (pinfunction "1_1") (pintype "input"))
      (node (ref "R3") (pin "1") (pinfunction "1_1") (pintype "input"))
      (node (ref "U3") (pin "21") (pinfunction "IO7_21") (pintype "unspecified"))
    )
    (net (code "18") (name "Net-(D4-A2)") (class "Default")
      (node (ref "D4") (pin "2") (pinfunction "A2_2") (pintype "unspecified"))
      (node (ref "Q2") (pin "1") (pinfunction "G_1") (pintype "unspecified"))
      (node (ref "RN2") (pin "3") (pinfunction "3_3") (pintype "unspecified"))
      (node (ref "RN3") (pin "1") (pinfunction "1_1") (pintype "input"))
    )
    (net (code "19") (name "Net-(D4-K)") (class "Default")
      (node (ref "C4") (pin "2") (pinfunction "2_2") (pintype "unspecified"))
      (node (ref "D4") (pin "3") (pinfunction "K_3") (pintype "unspecified"))
      (node (ref "SW1") (pin "2") (pinfunction "2_2") (pintype "unspecified"))
    )
    (net (code "20") (name "Net-(D5-A)") (class "Default")
      (node (ref "D5") (pin "2") (pinfunction "A_2") (pintype "input"))
      (node (ref "L1") (pin "1") (pinfunction "1_1") (pintype "input"))
      (node (ref "Q9") (pin "3") (pinfunction "C_3") (pintype "input"))
    )
    (net (code "21") (name "Net-(D5-K)") (class "Default")
      (node (ref "C12") (pin "1") (pinfunction "1_1") (pintype "input"))
      (node (ref "D5") (pin "1") (pinfunction "K_1") (pintype "input"))
      (node (ref "Q7") (pin "2") (pinfunction "E_2") (pintype "unspecified"))
      (node (ref "Q8") (pin "2") (pinfunction "E_2") (pintype "unspecified"))
    )
    (net (code "22") (name "Net-(OK1-A)") (class "Default")
      (node (ref "OK1") (pin "2") (pinfunction "A_2") (pintype "unspecified"))
      (node (ref "R2") (pin "1") (pinfunction "1_1") (pintype "input"))
      (node (ref "ing1") (pin "1") (pinfunction "+_1") (pintype "unspecified"))
    )
    (net (code "23") (name "Net-(OK1-K)") (class "Default")
      (node (ref "OK1") (pin "1") (pinfunction "K_1") (pintype "unspecified"))
      (node (ref "U1") (pin "5") (pinfunction "STDBY_5") (pintype "input"))
    )
    (net (code "24") (name "Net-(Q1-B)") (class "Default")
      (node (ref "Q1") (pin "1") (pinfunction "B_1") (pintype "unspecified"))
      (node (ref "RN2") (pin "1") (pinfunction "1_1") (pintype "unspecified"))
      (node (ref "RN3") (pin "7") (pinfunction "7_7") (pintype "input"))
    )
    (net (code "25") (name "Net-(Q1-C)") (class "Default")
      (node (ref "Q1") (pin "3") (pinfunction "C_3") (pintype "unspecified"))
      (node (ref "RN2") (pin "2") (pinfunction "2_2") (pintype "unspecified"))
    )
    (net (code "26") (name "Net-(Q3-B)") (class "Default")
      (node (ref "Q3") (pin "1") (pinfunction "B_1") (pintype "input"))
      (node (ref "RN6") (pin "3") (pinfunction "3_3") (pintype "unspecified"))
    )
    (net (code "27") (name "Net-(Q3-C)") (class "Default")
      (node (ref "Q3") (pin "3") (pinfunction "C_3") (pintype "input"))
      (node (ref "RN7") (pin "3") (pinfunction "3_3") (pintype "input"))
      (node (ref "RN7") (pin "4") (pinfunction "4_4") (pintype "input"))
    )
    (net (code "28") (name "Net-(Q4-B)") (class "Default")
      (node (ref "Q4") (pin "1") (pinfunction "B_1") (pintype "input"))
      (node (ref "RN6") (pin "4") (pinfunction "4_4") (pintype "unspecified"))
    )
    (net (code "29") (name "Net-(Q4-C)") (class "Default")
      (node (ref "Q4") (pin "3") (pinfunction "C_3") (pintype "input"))
      (node (ref "RN7") (pin "1") (pinfunction "1_1") (pintype "input"))
      (node (ref "RN7") (pin "2") (pinfunction "2_2") (pintype "input"))
    )
    (net (code "30") (name "Net-(Q5-B)") (class "Default")
      (node (ref "Q5") (pin "1") (pinfunction "B_1") (pintype "unspecified"))
      (node (ref "RN7") (pin "6") (pinfunction "6_6") (pintype "input"))
    )
    (net (code "31") (name "Net-(Q6-B)") (class "Default")
      (node (ref "Q6") (pin "1") (pinfunction "B_1") (pintype "unspecified"))
      (node (ref "RN7") (pin "7") (pinfunction "7_7") (pintype "input"))
    )
    (net (code "32") (name "Net-(Q7-B)") (class "Default")
      (node (ref "Q7") (pin "1") (pinfunction "B_1") (pintype "unspecified"))
      (node (ref "RN7") (pin "8") (pinfunction "8_8") (pintype "input"))
    )
    (net (code "33") (name "Net-(Q8-B)") (class "Default")
      (node (ref "Q8") (pin "1") (pinfunction "B_1") (pintype "unspecified"))
      (node (ref "RN7") (pin "5") (pinfunction "5_5") (pintype "input"))
    )
    (net (code "34") (name "Net-(Q9-B)") (class "Default")
      (node (ref "C11") (pin "2") (pinfunction "2_2") (pintype "input"))
      (node (ref "Q9") (pin "1") (pinfunction "B_1") (pintype "input"))
      (node (ref "R3") (pin "2") (pinfunction "2_2") (pintype "input"))
    )
    (net (code "35") (name "Net-(U1-PROG)") (class "Default")
      (node (ref "R1") (pin "1") (pinfunction "1_1") (pintype "input"))
      (node (ref "U1") (pin "6") (pinfunction "PROG_6") (pintype "input"))
    )
    (net (code "36") (name "Net-(U1-{slash}CHRG)") (class "Default")
      (node (ref "U1") (pin "1") (pinfunction "/CHRG_1") (pintype "input"))
      (node (ref "ing1") (pin "2") (pinfunction "-_2") (pintype "unspecified"))
    )
    (net (code "37") (name "Net-(USB1-CC1)") (class "Default")
      (node (ref "RN1") (pin "3") (pinfunction "3_3") (pintype "unspecified"))
      (node (ref "USB1") (pin "4") (pinfunction "CC1_4") (pintype "unspecified"))
    )
    (net (code "38") (name "Net-(USB1-CC2)") (class "Default")
      (node (ref "RN1") (pin "4") (pinfunction "4_4") (pintype "unspecified"))
      (node (ref "USB1") (pin "10") (pinfunction "CC2_10") (pintype "unspecified"))
    )
    (net (code "39") (name "OUT_A") (class "Default")
      (node (ref "CN1") (pin "1") (pinfunction "1_1") (pintype "unspecified"))
      (node (ref "CN1") (pin "11") (pinfunction "11_11") (pintype "unspecified"))
      (node (ref "CN1") (pin "3") (pinfunction "3_3") (pintype "unspecified"))
      (node (ref "CN1") (pin "4") (pinfunction "4_4") (pintype "unspecified"))
      (node (ref "D6") (pin "2") (pinfunction "2_2") (pintype "unspecified"))
      (node (ref "Q5") (pin "2") (pinfunction "E_2") (pintype "unspecified"))
      (node (ref "Q7") (pin "3") (pinfunction "C_3") (pintype "unspecified"))
    )
    (net (code "40") (name "OUT_B") (class "Default")
      (node (ref "CN1") (pin "10") (pinfunction "10_10") (pintype "unspecified"))
      (node (ref "CN1") (pin "2") (pinfunction "2_2") (pintype "unspecified"))
      (node (ref "D6") (pin "1") (pinfunction "1_1") (pintype "unspecified"))
      (node (ref "Q6") (pin "2") (pinfunction "E_2") (pintype "unspecified"))
      (node (ref "Q8") (pin "3") (pinfunction "C_3") (pintype "unspecified"))
    )
    (net (code "41") (name "USB_DN") (class "Default")
      (node (ref "D2") (pin "2") (pinfunction "2_2") (pintype "unspecified"))
      (node (ref "U3") (pin "26") (pinfunction "IO18_26") (pintype "unspecified"))
      (node (ref "USB1") (pin "5") (pinfunction "DN2_5") (pintype "unspecified"))
      (node (ref "USB1") (pin "7") (pinfunction "DN1_7") (pintype "unspecified"))
    )
    (net (code "42") (name "USB_DP") (class "Default")
      (node (ref "D1") (pin "2") (pinfunction "2_2") (pintype "unspecified"))
      (node (ref "U3") (pin "27") (pinfunction "IO19_27") (pintype "unspecified"))
      (node (ref "USB1") (pin "6") (pinfunction "DP1_6") (pintype "unspecified"))
      (node (ref "USB1") (pin "8") (pinfunction "DP2_8") (pintype "unspecified"))
    )
    (net (code "43") (name "VBAT") (class "Default")
      (node (ref "BAT1") (pin "2") (pinfunction "2_2") (pintype "unspecified"))
      (node (ref "C2") (pin "2") (pinfunction "2_2") (pintype "unspecified"))
      (node (ref "Q2") (pin "2") (pinfunction "S_2") (pintype "unspecified"))
      (node (ref "RN3") (pin "8") (pinfunction "8_8") (pintype "input"))
      (node (ref "U1") (pin "3") (pinfunction "BAT_3") (pintype "input"))
    )
    (net (code "44") (name "VBIN") (class "Default")
      (node (ref "C5") (pin "2") (pinfunction "2_2") (pintype "input"))
      (node (ref "C7") (pin "2") (pinfunction "2_2") (pintype "unspecified"))
      (node (ref "C8") (pin "2") (pinfunction "2_2") (pintype "unspecified"))
      (node (ref "L1") (pin "2") (pinfunction "2_2") (pintype "input"))
      (node (ref "LED1") (pin "4") (pinfunction "VDD_4") (pintype "unspecified"))
      (node (ref "Q2") (pin "3") (pinfunction "D_3") (pintype "unspecified"))
      (node (ref "RN4") (pin "7") (pinfunction "7_7") (pintype "input"))
      (node (ref "U2") (pin "3") (pinfunction "VIN_3") (pintype "unspecified"))
    )
    (net (code "45") (name "VBUS") (class "Default")
      (node (ref "C1") (pin "2") (pinfunction "2_2") (pintype "unspecified"))
      (node (ref "D3") (pin "1") (pinfunction "1_1") (pintype "unspecified"))
      (node (ref "R2") (pin "2") (pinfunction "2_2") (pintype "input"))
      (node (ref "U1") (pin "4") (pinfunction "VCC_4") (pintype "input"))
      (node (ref "USB1") (pin "11") (pinfunction "VBUS_11") (pintype "unspecified"))
      (node (ref "USB1") (pin "2") (pinfunction "VBUS_2") (pintype "unspecified"))
    )
    (net (code "46") (name "unconnected-(LED1-DO-Pad1)") (class "Default")
      (node (ref "LED1") (pin "1") (pinfunction "DO_1") (pintype "unspecified+no_connect"))
    )
    (net (code "47") (name "unconnected-(U3-NC-Pad4)") (class "Default")
      (node (ref "U3") (pin "4") (pinfunction "NC_4") (pintype "unspecified+no_connect"))
    )
    (net (code "48") (name "unconnected-(U3-NC-Pad7)") (class "Default")
      (node (ref "U3") (pin "7") (pinfunction "NC_7") (pintype "unspecified+no_connect"))
    )
    (net (code "49") (name "unconnected-(U3-NC-Pad9)") (class "Default")
      (node (ref "U3") (pin "9") (pinfunction "NC_9") (pintype "unspecified+no_connect"))
    )
    (net (code "50") (name "unconnected-(U3-NC-Pad10)") (class "Default")
      (node (ref "U3") (pin "10") (pinfunction "NC_10") (pintype "unspecified+no_connect"))
    )
    (net (code "51") (name "unconnected-(U3-NC-Pad15)") (class "Default")
      (node (ref "U3") (pin "15") (pinfunction "NC_15") (pintype "unspecified+no_connect"))
    )
    (net (code "52") (name "unconnected-(U3-NC-Pad17)") (class "Default")
      (node (ref "U3") (pin "17") (pinfunction "NC_17") (pintype "unspecified+no_connect"))
    )
    (net (code "53") (name "unconnected-(U3-NC-Pad24)") (class "Default")
      (node (ref "U3") (pin "24") (pinfunction "NC_24") (pintype "unspecified+no_connect"))
    )
    (net (code "54") (name "unconnected-(U3-NC-Pad25)") (class "Default")
      (node (ref "U3") (pin "25") (pinfunction "NC_25") (pintype "unspecified+no_connect"))
    )
    (net (code "55") (name "unconnected-(U3-NC-Pad28)") (class "Default")
      (node (ref "U3") (pin "28") (pinfunction "NC_28") (pintype "unspecified+no_connect"))
    )
    (net (code "56") (name "unconnected-(U3-NC-Pad29)") (class "Default")
      (node (ref "U3") (pin "29") (pinfunction "NC_29") (pintype "unspecified+no_connect"))
    )
    (net (code "57") (name "unconnected-(U3-NC-Pad32)") (class "Default")
      (node (ref "U3") (pin "32") (pinfunction "NC_32") (pintype "unspecified+no_connect"))
    )
    (net (code "58") (name "unconnected-(U3-NC-Pad33)") (class "Default")
      (node (ref "U3") (pin "33") (pinfunction "NC_33") (pintype "unspecified+no_connect"))
    )
    (net (code "59") (name "unconnected-(U3-NC-Pad34)") (class "Default")
      (node (ref "U3") (pin "34") (pinfunction "NC_34") (pintype "unspecified+no_connect"))
    )
    (net (code "60") (name "unconnected-(U3-NC-Pad35)") (class "Default")
      (node (ref "U3") (pin "35") (pinfunction "NC_35") (pintype "unspecified+no_connect"))
    )
    (net (code "61") (name "unconnected-(U4-ASCX-Pad3)") (class "Default")
      (node (ref "U4") (pin "3") (pinfunction "ASCX_3") (pintype "unspecified+no_connect"))
    )
    (net (code "62") (name "unconnected-(U4-ASDX-Pad2)") (class "Default")
      (node (ref "U4") (pin "2") (pinfunction "ASDX_2") (pintype "unspecified+no_connect"))
    )
    (net (code "63") (name "unconnected-(U4-CSB-Pad12)") (class "Default")
      (node (ref "U4") (pin "12") (pinfunction "CSB_12") (pintype "unspecified+no_connect"))
    )
    (net (code "64") (name "unconnected-(U4-INT1-Pad4)") (class "Default")
      (node (ref "U4") (pin "4") (pinfunction "INT1_4") (pintype "unspecified+no_connect"))
    )
    (net (code "65") (name "unconnected-(U4-INT2-Pad9)") (class "Default")
      (node (ref "U4") (pin "9") (pinfunction "INT2_9") (pintype "unspecified+no_connect"))
    )
    (net (code "66") (name "unconnected-(U4-OCSB-Pad10)") (class "Default")
      (node (ref "U4") (pin "10") (pinfunction "OCSB_10") (pintype "unspecified+no_connect"))
    )
    (net (code "67") (name "unconnected-(U4-OSDO-Pad11)") (class "Default")
      (node (ref "U4") (pin "11") (pinfunction "OSDO_11") (pintype "unspecified+no_connect"))
    )
    (net (code "68") (name "unconnected-(USB1-SBU1-Pad9)") (class "Default")
      (node (ref "USB1") (pin "9") (pinfunction "SBU1_9") (pintype "unspecified+no_connect"))
    )
    (net (code "69") (name "unconnected-(USB1-SBU2-Pad3)") (class "Default")
      (node (ref "USB1") (pin "3") (pinfunction "SBU2_3") (pintype "unspecified+no_connect"))
    )
    (net (code "70") (name "unconnected-(USB1-SHELL-Pad13)") (class "Default")
      (node (ref "USB1") (pin "13") (pinfunction "SHELL_13") (pintype "unspecified+no_connect"))
    )
    (net (code "71") (name "unconnected-(USB1-SHELL-Pad14)") (class "Default")
      (node (ref "USB1") (pin "14") (pinfunction "SHELL_14") (pintype "unspecified+no_connect"))
    )
  )
)
